# delay.net
KiCad netlist of a schematic drawn in Altium Designer
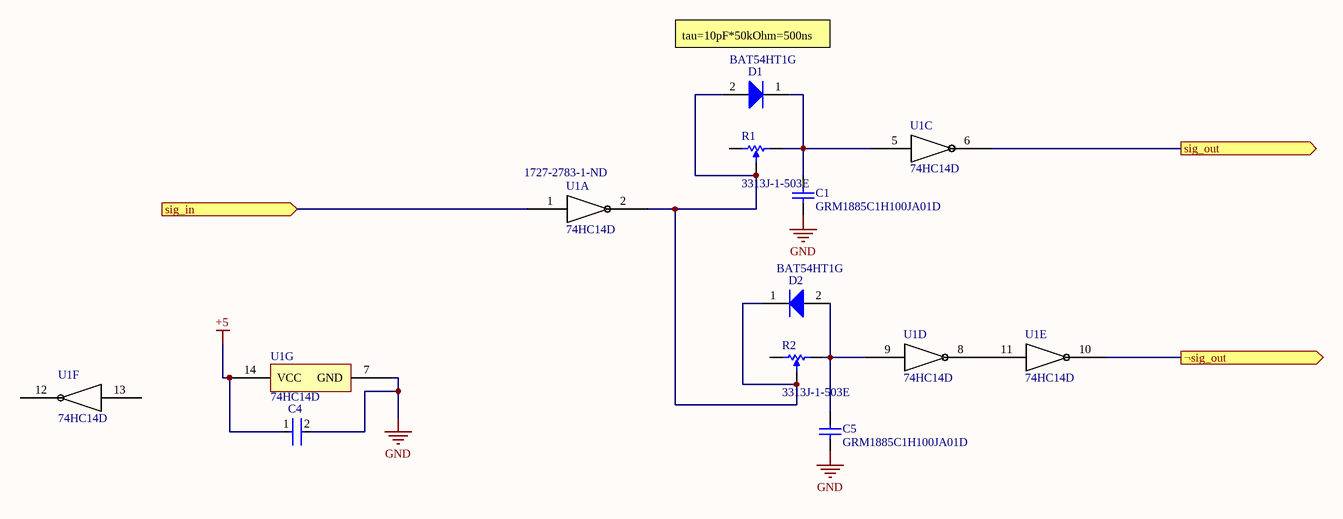
[diagram p0: delay.SchDoc]

(export (version "E")
  (design (tool "Eeschema 10.0.6"))
  (components
    (comp (ref "C1")
      (value "GRM1885C1H100JA01D")
      (footprint "CAPC1608X90X35LL10T15")
      (fields (field (name "MANUFACTURER") "Murata"))
      (libsource (lib "Altium Content Vault") (part "CAP"))
    )
    (comp (ref "C4")
      (value "C0603X104K5RACTU")
      (footprint "FP-C0603-CJ-MFG")
      (description "CAP CER 0.1UF 50V X7R 0603")
      (fields (field (name "VOLTAGE") "50V") (field (name "MANUFACTURER") "Kemet"))
      (libsource (lib "Altium Content Vault") (part "11868f565c42a9108669ba33697ecf6"))
    )
    (comp (ref "C5")
      (value "GRM1885C1H100JA01D")
      (footprint "CAPC1608X90X35LL10T15")
      (fields (field (name "MANUFACTURER") "Murata"))
      (libsource (lib "Altium Content Vault") (part "CAP"))
    )
    (comp (ref "D1")
      (value "BAT54HT1G")
      (footprint "ONSC-SOD-323-2-477-02_V")
      (description "Schottky Barrier Diode, 2-Pin SOD-323, Pb-Free, Tape and Reel")
      (fields (field (name "MANUFACTURER") "On Semiconductor"))
      (libsource (lib "Altium Content Vault") (part "ONSC-D-K1A2-2"))
    )
    (comp (ref "D2")
      (value "BAT54HT1G")
      (footprint "ONSC-SOD-323-2-477-02_V")
      (description "Schottky Barrier Diode, 2-Pin SOD-323, Pb-Free, Tape and Reel")
      (fields (field (name "MANUFACTURER") "On Semiconductor"))
      (libsource (lib "Altium Content Vault") (part "ONSC-D-K1A2-2"))
    )
    (comp (ref "R1")
      (value "3313J-1-503E")
      (footprint "BOUR-3313J-1_V")
      (fields (field (name "MANUFACTURER") "Bourns"))
      (libsource (lib "Altium Content Vault") (part "RES-ADJ-3_A"))
    )
    (comp (ref "R2")
      (value "3313J-1-503E")
      (footprint "BOUR-3313J-1_V")
      (fields (field (name "MANUFACTURER") "Bourns"))
      (libsource (lib "Altium Content Vault") (part "RES-ADJ-3_A"))
    )
    (comp (ref "U1")
      (value "74HC14D")
      (footprint "SOP14_narrow")
      (fields (field (name "SUPPLIER PART NUMBER 1") "1727-2783-1-ND"))
      (libsource (lib "coil_driver_lib") (part "74HC14D"))
    )
  )
  (nets
    (net (code "1") (name "+5") (class "Default")
      (node (ref "C4") (pin "1") (pinfunction "1_1") (pintype "passive"))
      (node (ref "U1") (pin "14") (pinfunction "VCC_14") (pintype "passive"))
    )
    (net (code "2") (name "/sig_in") (class "Default")
      (node (ref "U1") (pin "1") (pinfunction "1A_1") (pintype "passive"))
    )
    (net (code "3") (name "/sig_out") (class "Default")
      (node (ref "U1") (pin "6") (pinfunction "3Y_6") (pintype "passive"))
    )
    (net (code "4") (name "/¬sig_out") (class "Default")
      (node (ref "U1") (pin "10") (pinfunction "5Y_10") (pintype "passive"))
    )
    (net (code "5") (name "GND") (class "Default")
      (node (ref "C1") (pin "1") (pinfunction "1_1") (pintype "passive"))
      (node (ref "C4") (pin "2") (pinfunction "2_2") (pintype "passive"))
      (node (ref "C5") (pin "1") (pinfunction "1_1") (pintype "passive"))
      (node (ref "U1") (pin "7") (pinfunction "GND_7") (pintype "passive"))
    )
    (net (code "6") (name "Net-(D1-A)") (class "Default")
      (node (ref "D1") (pin "2") (pinfunction "A_2") (pintype "passive"))
      (node (ref "D2") (pin "1") (pinfunction "K_1") (pintype "passive"))
      (node (ref "R1") (pin "2") (pinfunction "2_2") (pintype "passive"))
      (node (ref "R2") (pin "2") (pinfunction "2_2") (pintype "passive"))
      (node (ref "U1") (pin "2") (pinfunction "1Y_2") (pintype "passive"))
    )
    (net (code "7") (name "Net-(D1-K)") (class "Default")
      (node (ref "C1") (pin "2") (pinfunction "2_2") (pintype "passive"))
      (node (ref "D1") (pin "1") (pinfunction "K_1") (pintype "passive"))
      (node (ref "R1") (pin "3") (pinfunction "3_3") (pintype "passive"))
      (node (ref "U1") (pin "5") (pinfunction "3A_5") (pintype "passive"))
    )
    (net (code "8") (name "Net-(D2-A)") (class "Default")
      (node (ref "C5") (pin "2") (pinfunction "2_2") (pintype "passive"))
      (node (ref "D2") (pin "2") (pinfunction "A_2") (pintype "passive"))
      (node (ref "R2") (pin "3") (pinfunction "3_3") (pintype "passive"))
      (node (ref "U1") (pin "9") (pinfunction "4A_9") (pintype "passive"))
    )
    (net (code "9") (name "Net-(U1D-4Y)") (class "Default")
      (node (ref "U1") (pin "11") (pinfunction "5A_11") (pintype "passive"))
      (node (ref "U1") (pin "8") (pinfunction "4Y_8") (pintype "passive"))
    )
    (net (code "10") (name "unconnected-(R1-Pad1)") (class "Default")
      (node (ref "R1") (pin "1") (pinfunction "1_1") (pintype "passive"))
    )
    (net (code "11") (name "unconnected-(R2-Pad1)") (class "Default")
      (node (ref "R2") (pin "1") (pinfunction "1_1") (pintype "passive"))
    )
    (net (code "12") (name "unconnected-(U1F-6A-Pad13)") (class "Default")
      (node (ref "U1") (pin "13") (pinfunction "6A_13") (pintype "passive"))
    )
    (net (code "13") (name "unconnected-(U1F-6Y-Pad12)") (class "Default")
      (node (ref "U1") (pin "12") (pinfunction "6Y_12") (pintype "passive"))
    )
  )
)
